# Sheet2.net
KiCad netlist of a schematic drawn in Altium Designer
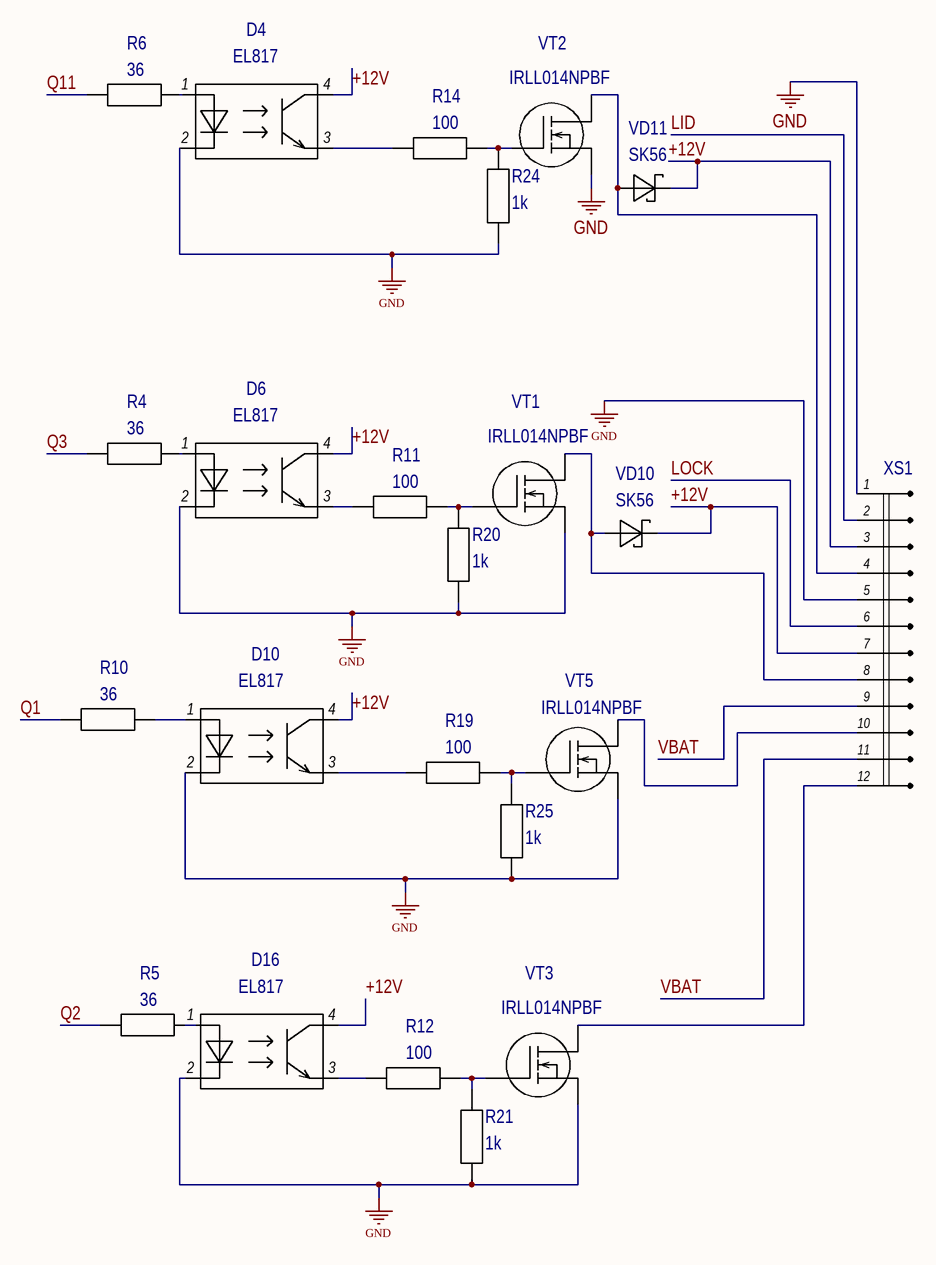
[diagram p0: Sheet2.SchDoc]

(export (version "E")
  (design (tool "Eeschema 10.0.6"))
  (components
    (comp (ref "D4")
      (value "EL817")
      (footprint "SOP254P1030X390-4N")
      (libsource (lib "Common_components") (part "OPTRONE_NPN"))
    )
    (comp (ref "D6")
      (value "EL817")
      (footprint "SOP254P1030X390-4N")
      (libsource (lib "Common_components") (part "OPTRONE_NPN"))
    )
    (comp (ref "D10")
      (value "EL817")
      (footprint "SOP254P1030X390-4N")
      (libsource (lib "Common_components") (part "OPTRONE_NPN"))
    )
    (comp (ref "D16")
      (value "EL817")
      (footprint "SOP254P1030X390-4N")
      (libsource (lib "Common_components") (part "OPTRONE_NPN"))
    )
    (comp (ref "R4")
      (value "36")
      (footprint "R_0603_(1608)")
      (fields (field (name "TOLERANCE") "5%"))
      (libsource (lib "Own_lib") (part "R"))
    )
    (comp (ref "R5")
      (value "36")
      (footprint "R_0603_(1608)")
      (fields (field (name "TOLERANCE") "5%"))
      (libsource (lib "Own_lib") (part "R"))
    )
    (comp (ref "R6")
      (value "36")
      (footprint "R_0603_(1608)")
      (fields (field (name "TOLERANCE") "5%"))
      (libsource (lib "Own_lib") (part "R"))
    )
    (comp (ref "R10")
      (value "36")
      (footprint "R_0603_(1608)")
      (fields (field (name "TOLERANCE") "5%"))
      (libsource (lib "Own_lib") (part "R"))
    )
    (comp (ref "R11")
      (value "100")
      (footprint "R_0603_(1608)")
      (fields (field (name "TOLERANCE") "5%"))
      (libsource (lib "") (part "R_1"))
    )
    (comp (ref "R12")
      (value "100")
      (footprint "R_0603_(1608)")
      (fields (field (name "TOLERANCE") "5%"))
      (libsource (lib "") (part "R_1"))
    )
    (comp (ref "R14")
      (value "100")
      (footprint "R_0603_(1608)")
      (fields (field (name "TOLERANCE") "5%"))
      (libsource (lib "") (part "R_1"))
    )
    (comp (ref "R19")
      (value "100")
      (footprint "R_0603_(1608)")
      (fields (field (name "TOLERANCE") "5%"))
      (libsource (lib "") (part "R_1"))
    )
    (comp (ref "R20")
      (value "1k")
      (footprint "R_0603_(1608)")
      (fields (field (name "TOLERANCE") "5%"))
      (libsource (lib "") (part "R_2"))
    )
    (comp (ref "R21")
      (value "1k")
      (footprint "R_0603_(1608)")
      (fields (field (name "TOLERANCE") "5%"))
      (libsource (lib "") (part "R_2"))
    )
    (comp (ref "R24")
      (value "1k")
      (footprint "R_0603_(1608)")
      (fields (field (name "TOLERANCE") "5%"))
      (libsource (lib "") (part "R_2"))
    )
    (comp (ref "R25")
      (value "1k")
      (footprint "R_0603_(1608)")
      (fields (field (name "TOLERANCE") "5%"))
      (libsource (lib "") (part "R_2"))
    )
    (comp (ref "VD10")
      (value "SK56")
      (footprint "DIONM5236X261N")
      (description "https://www.chipdip.ru/product/sk56")
      (libsource (lib "sch_RU") (part "Schottky"))
    )
    (comp (ref "VD11")
      (value "SK56")
      (footprint "DIONM5236X261N")
      (description "https://www.chipdip.ru/product/sk56")
      (libsource (lib "sch_RU") (part "Schottky"))
    )
    (comp (ref "VT1")
      (value "IRLL014NPBF")
      (footprint "SOT-223(BCE)")
      (libsource (lib "Own_lib") (part "IRLL014NPBF"))
    )
    (comp (ref "VT2")
      (value "IRLL014NPBF")
      (footprint "SOT-223(BCE)")
      (libsource (lib "Own_lib") (part "IRLL014NPBF"))
    )
    (comp (ref "VT3")
      (value "IRLL014NPBF")
      (footprint "SOT-223(BCE)")
      (libsource (lib "Own_lib") (part "IRLL014NPBF"))
    )
    (comp (ref "VT5")
      (value "IRLL014NPBF")
      (footprint "SOT-223(BCE)")
      (libsource (lib "Own_lib") (part "IRLL014NPBF"))
    )
    (comp (ref "XS1")
      (value "Pad 1x12")
      (footprint "PLS-12(NO_3D)")
      (libsource (lib "Connectors") (part "Pad 1x12"))
    )
  )
  (nets
    (net (code "1") (name "/+12V") (class "Default")
      (node (ref "D10") (pin "4") (pinfunction "4_4") (pintype "passive"))
      (node (ref "D16") (pin "4") (pinfunction "4_4") (pintype "passive"))
      (node (ref "D4") (pin "4") (pinfunction "4_4") (pintype "passive"))
      (node (ref "D6") (pin "4") (pinfunction "4_4") (pintype "passive"))
      (node (ref "VD10") (pin "1") (pinfunction "1_1") (pintype "passive"))
      (node (ref "VD11") (pin "1") (pinfunction "1_1") (pintype "passive"))
      (node (ref "XS1") (pin "3") (pinfunction "3_3") (pintype "passive"))
      (node (ref "XS1") (pin "7") (pinfunction "7_7") (pintype "passive"))
    )
    (net (code "2") (name "/LID") (class "Default")
      (node (ref "XS1") (pin "2") (pinfunction "2_2") (pintype "passive"))
    )
    (net (code "3") (name "/LOCK") (class "Default")
      (node (ref "XS1") (pin "6") (pinfunction "6_6") (pintype "passive"))
    )
    (net (code "4") (name "/Q1") (class "Default")
      (node (ref "R10") (pin "2") (pinfunction "2_2") (pintype "passive"))
    )
    (net (code "5") (name "/Q2") (class "Default")
      (node (ref "R5") (pin "2") (pinfunction "2_2") (pintype "passive"))
    )
    (net (code "6") (name "/Q3") (class "Default")
      (node (ref "R4") (pin "2") (pinfunction "2_2") (pintype "passive"))
    )
    (net (code "7") (name "/Q11") (class "Default")
      (node (ref "R6") (pin "2") (pinfunction "2_2") (pintype "passive"))
    )
    (net (code "8") (name "/VBAT") (class "Default")
      (node (ref "XS1") (pin "11") (pinfunction "11_11") (pintype "passive"))
      (node (ref "XS1") (pin "9") (pinfunction "9_9") (pintype "passive"))
    )
    (net (code "9") (name "GND") (class "Default")
      (node (ref "D10") (pin "2") (pinfunction "2_2") (pintype "passive"))
      (node (ref "D16") (pin "2") (pinfunction "2_2") (pintype "passive"))
      (node (ref "D4") (pin "2") (pinfunction "2_2") (pintype "passive"))
      (node (ref "D6") (pin "2") (pinfunction "2_2") (pintype "passive"))
      (node (ref "R20") (pin "2") (pinfunction "2_2") (pintype "passive"))
      (node (ref "R21") (pin "2") (pinfunction "2_2") (pintype "passive"))
      (node (ref "R24") (pin "2") (pinfunction "2_2") (pintype "passive"))
      (node (ref "R25") (pin "2") (pinfunction "2_2") (pintype "passive"))
      (node (ref "VT1") (pin "3") (pinfunction "S_3") (pintype "passive"))
      (node (ref "VT2") (pin "3") (pinfunction "S_3") (pintype "passive"))
      (node (ref "VT3") (pin "3") (pinfunction "S_3") (pintype "passive"))
      (node (ref "VT5") (pin "3") (pinfunction "S_3") (pintype "passive"))
      (node (ref "XS1") (pin "1") (pinfunction "1_1") (pintype "passive"))
      (node (ref "XS1") (pin "5") (pinfunction "5_5") (pintype "passive"))
    )
    (net (code "10") (name "Net-(D4-Pad1)") (class "Default")
      (node (ref "D4") (pin "1") (pinfunction "1_1") (pintype "passive"))
      (node (ref "R6") (pin "1") (pinfunction "1_1") (pintype "passive"))
    )
    (net (code "11") (name "Net-(D4-Pad3)") (class "Default")
      (node (ref "D4") (pin "3") (pinfunction "3_3") (pintype "passive"))
      (node (ref "R14") (pin "1") (pinfunction "1_1") (pintype "passive"))
    )
    (net (code "12") (name "Net-(D6-Pad1)") (class "Default")
      (node (ref "D6") (pin "1") (pinfunction "1_1") (pintype "passive"))
      (node (ref "R4") (pin "1") (pinfunction "1_1") (pintype "passive"))
    )
    (net (code "13") (name "Net-(D6-Pad3)") (class "Default")
      (node (ref "D6") (pin "3") (pinfunction "3_3") (pintype "passive"))
      (node (ref "R11") (pin "1") (pinfunction "1_1") (pintype "passive"))
    )
    (net (code "14") (name "Net-(D10-Pad1)") (class "Default")
      (node (ref "D10") (pin "1") (pinfunction "1_1") (pintype "passive"))
      (node (ref "R10") (pin "1") (pinfunction "1_1") (pintype "passive"))
    )
    (net (code "15") (name "Net-(D10-Pad3)") (class "Default")
      (node (ref "D10") (pin "3") (pinfunction "3_3") (pintype "passive"))
      (node (ref "R19") (pin "1") (pinfunction "1_1") (pintype "passive"))
    )
    (net (code "16") (name "Net-(D16-Pad1)") (class "Default")
      (node (ref "D16") (pin "1") (pinfunction "1_1") (pintype "passive"))
      (node (ref "R5") (pin "1") (pinfunction "1_1") (pintype "passive"))
    )
    (net (code "17") (name "Net-(D16-Pad3)") (class "Default")
      (node (ref "D16") (pin "3") (pinfunction "3_3") (pintype "passive"))
      (node (ref "R12") (pin "1") (pinfunction "1_1") (pintype "passive"))
    )
    (net (code "18") (name "Net-(VT1-D)") (class "Default")
      (node (ref "VD10") (pin "2") (pinfunction "2_2") (pintype "passive"))
      (node (ref "VT1") (pin "2") (pinfunction "D_2") (pintype "passive"))
      (node (ref "XS1") (pin "8") (pinfunction "8_8") (pintype "passive"))
    )
    (net (code "19") (name "Net-(VT1-G)") (class "Default")
      (node (ref "R11") (pin "2") (pinfunction "2_2") (pintype "passive"))
      (node (ref "R20") (pin "1") (pinfunction "1_1") (pintype "passive"))
      (node (ref "VT1") (pin "1") (pinfunction "G_1") (pintype "passive"))
    )
    (net (code "20") (name "Net-(VT2-D)") (class "Default")
      (node (ref "VD11") (pin "2") (pinfunction "2_2") (pintype "passive"))
      (node (ref "VT2") (pin "2") (pinfunction "D_2") (pintype "passive"))
      (node (ref "XS1") (pin "4") (pinfunction "4_4") (pintype "passive"))
    )
    (net (code "21") (name "Net-(VT2-G)") (class "Default")
      (node (ref "R14") (pin "2") (pinfunction "2_2") (pintype "passive"))
      (node (ref "R24") (pin "1") (pinfunction "1_1") (pintype "passive"))
      (node (ref "VT2") (pin "1") (pinfunction "G_1") (pintype "passive"))
    )
    (net (code "22") (name "Net-(VT3-D)") (class "Default")
      (node (ref "VT3") (pin "2") (pinfunction "D_2") (pintype "passive"))
      (node (ref "XS1") (pin "12") (pinfunction "12_12") (pintype "passive"))
    )
    (net (code "23") (name "Net-(VT3-G)") (class "Default")
      (node (ref "R12") (pin "2") (pinfunction "2_2") (pintype "passive"))
      (node (ref "R21") (pin "1") (pinfunction "1_1") (pintype "passive"))
      (node (ref "VT3") (pin "1") (pinfunction "G_1") (pintype "passive"))
    )
    (net (code "24") (name "Net-(VT5-D)") (class "Default")
      (node (ref "VT5") (pin "2") (pinfunction "D_2") (pintype "passive"))
      (node (ref "XS1") (pin "10") (pinfunction "10_10") (pintype "passive"))
    )
    (net (code "25") (name "Net-(VT5-G)") (class "Default")
      (node (ref "R19") (pin "2") (pinfunction "2_2") (pintype "passive"))
      (node (ref "R25") (pin "1") (pinfunction "1_1") (pintype "passive"))
      (node (ref "VT5") (pin "1") (pinfunction "G_1") (pintype "passive"))
    )
  )
)
